# AugmentedStethoscope_v1.net
KiCad netlist of a schematic drawn in EAGLE
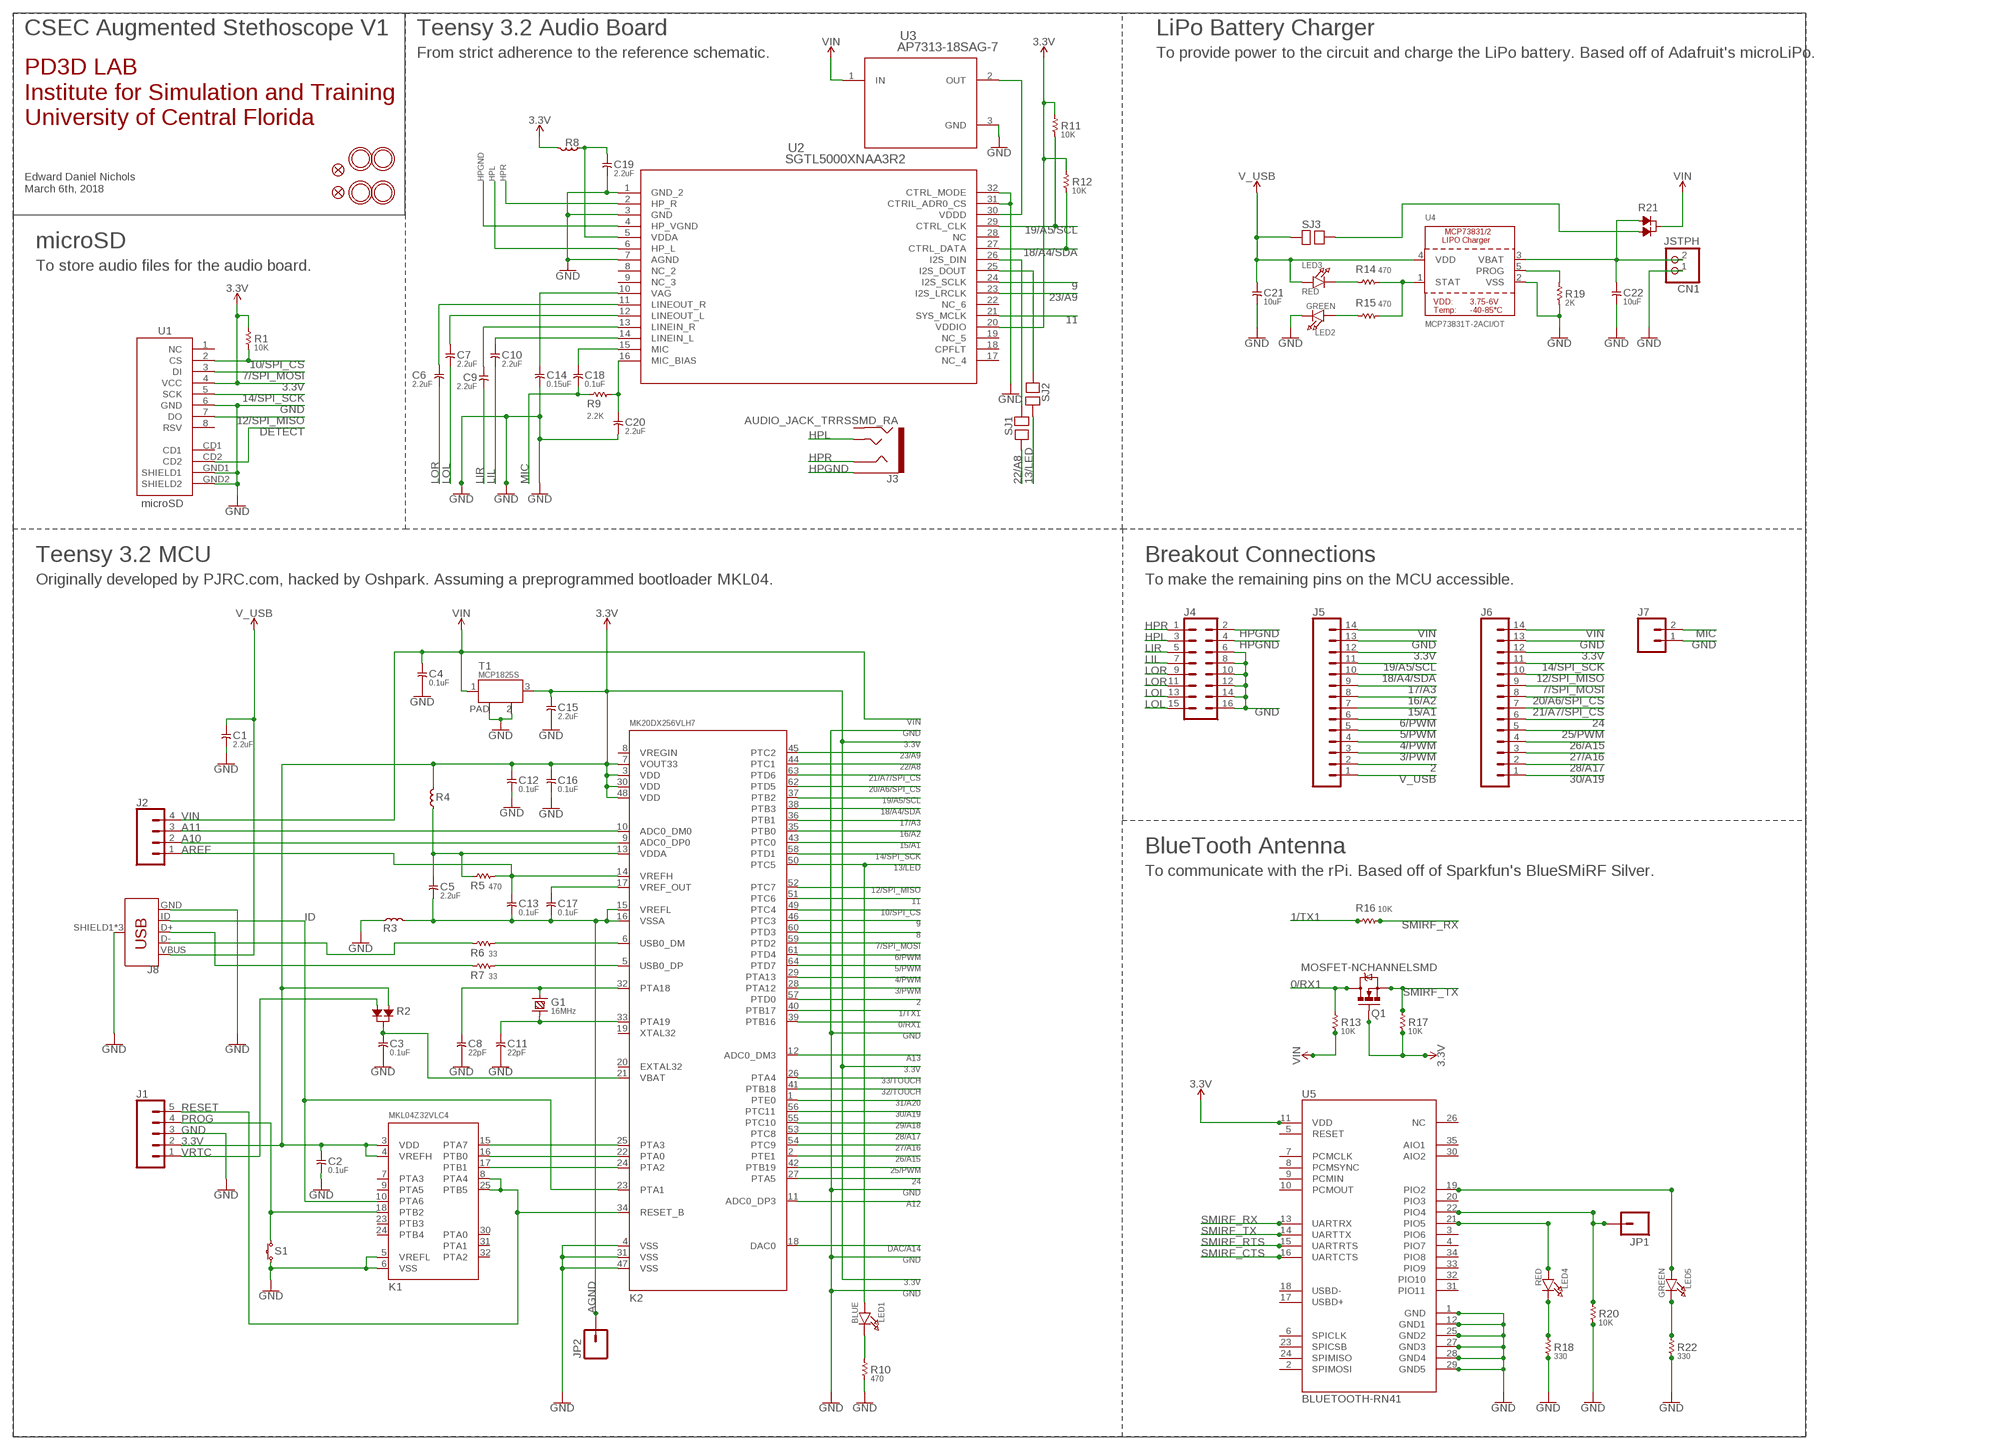
[diagram p0: schematic, sheet 1]

(export (version "E")
  (design (tool "Eeschema 10.0.6"))
  (components
    (comp (ref "C1")
      (value "2.2uF")
      (footprint "eagle-import:C0805")
      (fields (field (name "MF") "Taiyo Yuden") (field (name "MPN") "TMK212B7225KG-TR"))
      (libsource (lib "eagle-import") (part "CAPACITOR-2.2UF"))
    )
    (comp (ref "C2")
      (value "0.1uF")
      (footprint "eagle-import:C0603")
      (fields (field (name "MF") "Murata Electronics") (field (name "MPN") "GRM188R71C104KA01D"))
      (libsource (lib "eagle-import") (part "CAPACITOR-0.1UF"))
    )
    (comp (ref "C3")
      (value "0.1uF")
      (footprint "eagle-import:C0603")
      (fields (field (name "MF") "Murata Electronics") (field (name "MPN") "GRM188R71C104KA01D"))
      (libsource (lib "eagle-import") (part "CAPACITOR-0.1UF"))
    )
    (comp (ref "C4")
      (value "0.1uF")
      (footprint "eagle-import:C0603")
      (fields (field (name "MF") "Murata Electronics") (field (name "MPN") "GRM188R71C104KA01D"))
      (libsource (lib "eagle-import") (part "CAPACITOR-0.1UF"))
    )
    (comp (ref "C5")
      (value "2.2uF")
      (footprint "eagle-import:C0805")
      (fields (field (name "MF") "Taiyo Yuden") (field (name "MPN") "TMK212B7225KG-TR"))
      (libsource (lib "eagle-import") (part "CAPACITOR-2.2UF"))
    )
    (comp (ref "C6")
      (value "2.2uF")
      (footprint "eagle-import:C0805")
      (fields (field (name "MF") "Taiyo Yuden") (field (name "MPN") "TMK212B7225KG-TR"))
      (libsource (lib "eagle-import") (part "CAPACITOR-2.2UF"))
    )
    (comp (ref "C7")
      (value "2.2uF")
      (footprint "eagle-import:C0805")
      (fields (field (name "MF") "Taiyo Yuden") (field (name "MPN") "TMK212B7225KG-TR"))
      (libsource (lib "eagle-import") (part "CAPACITOR-2.2UF"))
    )
    (comp (ref "C8")
      (value "22pF")
      (footprint "eagle-import:C0603")
      (fields (field (name "MF") "Vishay / Vitramon") (field (name "MPN") "VJ0603A220JXACW1BC"))
      (libsource (lib "eagle-import") (part "CAPACITOR-22PF"))
    )
    (comp (ref "C9")
      (value "2.2uF")
      (footprint "eagle-import:C0805")
      (fields (field (name "MF") "Taiyo Yuden") (field (name "MPN") "TMK212B7225KG-TR"))
      (libsource (lib "eagle-import") (part "CAPACITOR-2.2UF"))
    )
    (comp (ref "C10")
      (value "2.2uF")
      (footprint "eagle-import:C0805")
      (fields (field (name "MF") "Taiyo Yuden") (field (name "MPN") "TMK212B7225KG-TR"))
      (libsource (lib "eagle-import") (part "CAPACITOR-2.2UF"))
    )
    (comp (ref "C11")
      (value "22pF")
      (footprint "eagle-import:C0603")
      (fields (field (name "MF") "Vishay / Vitramon") (field (name "MPN") "VJ0603A220JXACW1BC"))
      (libsource (lib "eagle-import") (part "CAPACITOR-22PF"))
    )
    (comp (ref "C12")
      (value "0.1uF")
      (footprint "eagle-import:C0603")
      (fields (field (name "MF") "Murata Electronics") (field (name "MPN") "GRM188R71C104KA01D"))
      (libsource (lib "eagle-import") (part "CAPACITOR-0.1UF"))
    )
    (comp (ref "C13")
      (value "0.1uF")
      (footprint "eagle-import:C0603")
      (fields (field (name "MF") "Murata Electronics") (field (name "MPN") "GRM188R71C104KA01D"))
      (libsource (lib "eagle-import") (part "CAPACITOR-0.1UF"))
    )
    (comp (ref "C14")
      (value "0.15uF")
      (footprint "eagle-import:C0805")
      (fields (field (name "MF") "Taiyo Yuden") (field (name "MPN") "TMK212B7225KG-TR"))
      (libsource (lib "eagle-import") (part "CAPACITOR-2.2UF"))
    )
    (comp (ref "C15")
      (value "2.2uF")
      (footprint "eagle-import:C0805")
      (fields (field (name "MF") "Taiyo Yuden") (field (name "MPN") "TMK212B7225KG-TR"))
      (libsource (lib "eagle-import") (part "CAPACITOR-2.2UF"))
    )
    (comp (ref "C16")
      (value "0.1uF")
      (footprint "eagle-import:C0603")
      (fields (field (name "MF") "Murata Electronics") (field (name "MPN") "GRM188R71C104KA01D"))
      (libsource (lib "eagle-import") (part "CAPACITOR-0.1UF"))
    )
    (comp (ref "C17")
      (value "0.1uF")
      (footprint "eagle-import:C0603")
      (fields (field (name "MF") "Murata Electronics") (field (name "MPN") "GRM188R71C104KA01D"))
      (libsource (lib "eagle-import") (part "CAPACITOR-0.1UF"))
    )
    (comp (ref "C18")
      (value "0.1uF")
      (footprint "eagle-import:C0805")
      (fields (field (name "MF") "Taiyo Yuden") (field (name "MPN") "TMK212B7225KG-TR"))
      (libsource (lib "eagle-import") (part "CAPACITOR-2.2UF"))
    )
    (comp (ref "C19")
      (value "2.2uF")
      (footprint "eagle-import:C0805")
      (fields (field (name "MF") "Taiyo Yuden") (field (name "MPN") "TMK212B7225KG-TR"))
      (libsource (lib "eagle-import") (part "CAPACITOR-2.2UF"))
    )
    (comp (ref "C20")
      (value "2.2uF")
      (footprint "eagle-import:C0805")
      (fields (field (name "MF") "Taiyo Yuden") (field (name "MPN") "TMK212B7225KG-TR"))
      (libsource (lib "eagle-import") (part "CAPACITOR-2.2UF"))
    )
    (comp (ref "C21")
      (value "10uF")
      (footprint "eagle-import:C0603")
      (fields (field (name "MF") "Murata Electronics") (field (name "MPN") "GRM188R71C104KA01D"))
      (libsource (lib "eagle-import") (part "CAPACITOR-0.1UF"))
    )
    (comp (ref "C22")
      (value "10uF")
      (footprint "eagle-import:C0603")
      (fields (field (name "MF") "Murata Electronics") (field (name "MPN") "GRM188R71C104KA01D"))
      (libsource (lib "eagle-import") (part "CAPACITOR-0.1UF"))
    )
    (comp (ref "CN1")
      (value "JSTPH")
      (footprint "eagle-import:JSTPH2")
      (libsource (lib "eagle-import") (part "JST_2PIN"))
    )
    (comp (ref "FID2")
      (value "FIDUCIAL\"\"")
      (footprint "eagle-import:FIDUCIAL_1MM")
      (libsource (lib "eagle-import") (part "FIDUCIAL{dblquote}{dblquote}"))
    )
    (comp (ref "FID3")
      (value "FIDUCIAL\"\"")
      (footprint "eagle-import:FIDUCIAL_1MM")
      (fields (field (name "BOM") "EXCLUDE"))
      (libsource (lib "eagle-import") (part "FIDUCIAL{dblquote}{dblquote}"))
    )
    (comp (ref "G1")
      (value "16MHz")
      (footprint "eagle-import:HC49US")
      (fields (field (name "MF") "ABRACON") (field (name "MPN") "ABL-16.000MHz-B1U"))
      (libsource (lib "eagle-import") (part "CRYSTAL-HC49US"))
    )
    (comp (ref "J1")
      (value "CONN_05")
      (footprint "eagle-import:1X05")
      (libsource (lib "eagle-import") (part "CONN_05"))
    )
    (comp (ref "J2")
      (value "CONN_04")
      (footprint "eagle-import:1X04")
      (libsource (lib "eagle-import") (part "CONN_04"))
    )
    (comp (ref "J3")
      (value "AUDIO_JACK_TRRSSMD_RA")
      (footprint "eagle-import:AUDIO_JACK_3.5MM_TRRS_SMD_RA")
      (libsource (lib "eagle-import") (part "AUDIO_JACK_TRRSSMD_RA"))
    )
    (comp (ref "J4")
      (value "CONN_08X2")
      (footprint "eagle-import:2X8")
      (libsource (lib "eagle-import") (part "CONN_08X2"))
    )
    (comp (ref "J5")
      (value "CONN_14")
      (footprint "eagle-import:1X14")
      (libsource (lib "eagle-import") (part "CONN_14"))
    )
    (comp (ref "J6")
      (value "CONN_14")
      (footprint "eagle-import:1X14")
      (libsource (lib "eagle-import") (part "CONN_14"))
    )
    (comp (ref "J7")
      (value "CONN_02")
      (footprint "eagle-import:1X02")
      (libsource (lib "eagle-import") (part "CONN_02"))
    )
    (comp (ref "J8")
      (value "USB_MICRO-B_FEMALE-SMT")
      (footprint "eagle-import:USB-B-MICRO-SMD")
      (libsource (lib "eagle-import") (part "USB_MICRO-B_FEMALE-SMT"))
    )
    (comp (ref "JP1")
      (value "M01SMDNS")
      (footprint "eagle-import:1X01NS")
      (libsource (lib "eagle-import") (part "M01SMDNS"))
    )
    (comp (ref "JP2")
      (value "M01SMDNS")
      (footprint "eagle-import:1X01NS")
      (libsource (lib "eagle-import") (part "M01SMDNS"))
    )
    (comp (ref "K1")
      (value "MKL04Z32VLC4")
      (footprint "eagle-import:LQFP32-08")
      (fields (field (name "MF") "PJRC") (field (name "MPN") "IC_MKL04Z32_TQFP32"))
      (libsource (lib "eagle-import") (part "MKL04Z32VLC4"))
    )
    (comp (ref "K2")
      (value "MK20DX256VLH7")
      (footprint "eagle-import:LQFP64-05")
      (fields (field (name "MF") "NXP"))
      (libsource (lib "eagle-import") (part "MK20DX256VLH7"))
    )
    (comp (ref "LED1")
      (value "BLUE")
      (footprint "eagle-import:CHIPLED_0805")
      (libsource (lib "eagle-import") (part "LED0805"))
    )
    (comp (ref "LED2")
      (value "GREEN")
      (footprint "eagle-import:CHIPLED_0805")
      (libsource (lib "eagle-import") (part "LED0805"))
    )
    (comp (ref "LED3")
      (value "RED")
      (footprint "eagle-import:CHIPLED_0805")
      (libsource (lib "eagle-import") (part "LED0805"))
    )
    (comp (ref "LED4")
      (value "RED")
      (footprint "eagle-import:CHIPLED_0805")
      (libsource (lib "eagle-import") (part "LED0805"))
    )
    (comp (ref "LED5")
      (value "GREEN")
      (footprint "eagle-import:CHIPLED_0805")
      (libsource (lib "eagle-import") (part "LED0805"))
    )
    (comp (ref "Q1")
      (value "MOSFET-NCHANNELSMD")
      (footprint "eagle-import:SOT23-3")
      (libsource (lib "eagle-import") (part "MOSFET-NCHANNELSMD"))
    )
    (comp (ref "R1")
      (value "10K")
      (footprint "eagle-import:R0603")
      (fields (field (name "MF") "Vishay") (field (name "MPN") "CRCW0603470RFKEA"))
      (libsource (lib "eagle-import") (part "RESISTOR-470R"))
    )
    (comp (ref "R2")
      (value "DIODE_DUAL")
      (footprint "eagle-import:SOT-23")
      (fields (field (name "MF") "NXP Semiconductors") (field (name "MPN") "BAT54C,215"))
      (libsource (lib "eagle-import") (part "DIODE_DUAL"))
    )
    (comp (ref "R3")
      (value "FERRITE")
      (footprint "eagle-import:L0603")
      (fields (field (name "MF") "Murata Electronics") (field (name "MPN") " BLM18AG601SN1D"))
      (libsource (lib "eagle-import") (part "FERRITE"))
    )
    (comp (ref "R4")
      (value "FERRITE")
      (footprint "eagle-import:L0603")
      (fields (field (name "MF") "Murata Electronics") (field (name "MPN") " BLM18AG601SN1D"))
      (libsource (lib "eagle-import") (part "FERRITE"))
    )
    (comp (ref "R5")
      (value "470")
      (footprint "eagle-import:R0603")
      (fields (field (name "MF") "Vishay") (field (name "MPN") "CRCW0603470RFKEA"))
      (libsource (lib "eagle-import") (part "RESISTOR-470R"))
    )
    (comp (ref "R6")
      (value "33")
      (footprint "eagle-import:R0603")
      (fields (field (name "MF") "Panasonic") (field (name "MPN") "ERJ-PA3F33R0V"))
      (libsource (lib "eagle-import") (part "RESISTOR-33R"))
    )
    (comp (ref "R7")
      (value "33")
      (footprint "eagle-import:R0603")
      (fields (field (name "MF") "Panasonic") (field (name "MPN") "ERJ-PA3F33R0V"))
      (libsource (lib "eagle-import") (part "RESISTOR-33R"))
    )
    (comp (ref "R8")
      (value "FERRITE")
      (footprint "eagle-import:L0603")
      (fields (field (name "MF") "Murata Electronics") (field (name "MPN") " BLM18AG601SN1D"))
      (libsource (lib "eagle-import") (part "FERRITE"))
    )
    (comp (ref "R9")
      (value "2.2K")
      (footprint "eagle-import:R0603")
      (fields (field (name "MF") "Vishay") (field (name "MPN") "CRCW0603470RFKEA"))
      (libsource (lib "eagle-import") (part "RESISTOR-470R"))
    )
    (comp (ref "R10")
      (value "470")
      (footprint "eagle-import:R0603")
      (fields (field (name "MF") "Vishay") (field (name "MPN") "CRCW0603470RFKEA"))
      (libsource (lib "eagle-import") (part "RESISTOR-470R"))
    )
    (comp (ref "R11")
      (value "10K")
      (footprint "eagle-import:R0603")
      (fields (field (name "MF") "Vishay") (field (name "MPN") "CRCW0603470RFKEA"))
      (libsource (lib "eagle-import") (part "RESISTOR-470R"))
    )
    (comp (ref "R12")
      (value "10K")
      (footprint "eagle-import:R0603")
      (fields (field (name "MF") "Vishay") (field (name "MPN") "CRCW0603470RFKEA"))
      (libsource (lib "eagle-import") (part "RESISTOR-470R"))
    )
    (comp (ref "R13")
      (value "10K")
      (footprint "eagle-import:R0603")
      (fields (field (name "MF") "Vishay") (field (name "MPN") "CRCW0603470RFKEA"))
      (libsource (lib "eagle-import") (part "RESISTOR-470R"))
    )
    (comp (ref "R14")
      (value "470")
      (footprint "eagle-import:R0603")
      (fields (field (name "MF") "Panasonic") (field (name "MPN") "ERJ-PA3F33R0V"))
      (libsource (lib "eagle-import") (part "RESISTOR-33R"))
    )
    (comp (ref "R15")
      (value "470")
      (footprint "eagle-import:R0603")
      (fields (field (name "MF") "Panasonic") (field (name "MPN") "ERJ-PA3F33R0V"))
      (libsource (lib "eagle-import") (part "RESISTOR-33R"))
    )
    (comp (ref "R16")
      (value "10K")
      (footprint "eagle-import:R0603")
      (fields (field (name "MF") "Panasonic") (field (name "MPN") "ERJ-PA3F33R0V"))
      (libsource (lib "eagle-import") (part "RESISTOR-33R"))
    )
    (comp (ref "R17")
      (value "10K")
      (footprint "eagle-import:R0603")
      (fields (field (name "MF") "Vishay") (field (name "MPN") "CRCW0603470RFKEA"))
      (libsource (lib "eagle-import") (part "RESISTOR-470R"))
    )
    (comp (ref "R18")
      (value "330")
      (footprint "eagle-import:R0603")
      (fields (field (name "MF") "Vishay") (field (name "MPN") "CRCW0603470RFKEA"))
      (libsource (lib "eagle-import") (part "RESISTOR-470R"))
    )
    (comp (ref "R19")
      (value "2K")
      (footprint "eagle-import:R0603")
      (fields (field (name "MF") "Vishay") (field (name "MPN") "CRCW0603470RFKEA"))
      (libsource (lib "eagle-import") (part "RESISTOR-470R"))
    )
    (comp (ref "R20")
      (value "10K")
      (footprint "eagle-import:R0603")
      (fields (field (name "MF") "Vishay") (field (name "MPN") "CRCW0603470RFKEA"))
      (libsource (lib "eagle-import") (part "RESISTOR-470R"))
    )
    (comp (ref "R21")
      (value "DIODE_DUAL")
      (footprint "eagle-import:SOT-23")
      (fields (field (name "MF") "NXP Semiconductors") (field (name "MPN") "BAT54C,215"))
      (libsource (lib "eagle-import") (part "DIODE_DUAL"))
    )
    (comp (ref "R22")
      (value "330")
      (footprint "eagle-import:R0603")
      (fields (field (name "MF") "Vishay") (field (name "MPN") "CRCW0603470RFKEA"))
      (libsource (lib "eagle-import") (part "RESISTOR-470R"))
    )
    (comp (ref "S1")
      (value "TACT_SWITCH")
      (footprint "eagle-import:ALPS_SKHH")
      (fields (field (name "MF") "ALPS") (field (name "MPN") "SKHHPKA010"))
      (libsource (lib "eagle-import") (part "TACT_SWITCH"))
    )
    (comp (ref "SJ1")
      (value "SOLDERJUMPER")
      (footprint "eagle-import:SOLDERJUMPER")
      (libsource (lib "eagle-import") (part "SOLDERJUMPER"))
    )
    (comp (ref "SJ2")
      (value "SOLDERJUMPER")
      (footprint "eagle-import:SOLDERJUMPER")
      (libsource (lib "eagle-import") (part "SOLDERJUMPER"))
    )
    (comp (ref "SJ3")
      (value "SOLDERJUMPER")
      (footprint "eagle-import:SOLDERJUMPER")
      (libsource (lib "eagle-import") (part "SOLDERJUMPER"))
    )
    (comp (ref "T1")
      (value "MCP1825S")
      (footprint "eagle-import:SOT-223")
      (fields (field (name "MF") "Microchip Technology") (field (name "MPN") "MCP1825S-3302E/DB"))
      (libsource (lib "eagle-import") (part "LDO"))
    )
    (comp (ref "U$1")
      (value "MOUNTINGHOLE2.5")
      (footprint "eagle-import:MOUNTINGHOLE_2.5_PLATED")
      (libsource (lib "eagle-import") (part "MOUNTINGHOLE2.5"))
    )
    (comp (ref "U$15")
      (value "MOUNTINGHOLE2.5")
      (footprint "eagle-import:MOUNTINGHOLE_2.5_PLATED")
      (libsource (lib "eagle-import") (part "MOUNTINGHOLE2.5"))
    )
    (comp (ref "U$17")
      (value "MOUNTINGHOLE2.5")
      (footprint "eagle-import:MOUNTINGHOLE_2.5_PLATED")
      (libsource (lib "eagle-import") (part "MOUNTINGHOLE2.5"))
    )
    (comp (ref "U$18")
      (value "MOUNTINGHOLE2.5")
      (footprint "eagle-import:MOUNTINGHOLE_2.5_PLATED")
      (libsource (lib "eagle-import") (part "MOUNTINGHOLE2.5"))
    )
    (comp (ref "U1")
      (value "microSD")
      (footprint "eagle-import:MICRO-SD-SOCKET-PP")
      (libsource (lib "eagle-import") (part "USD-SOCKETSMD"))
    )
    (comp (ref "U2")
      (value "SGTL5000XNAA3R2")
      (footprint "eagle-import:QFN32")
      (libsource (lib "eagle-import") (part "SGTL5000XNAA3R2"))
    )
    (comp (ref "U3")
      (value "AP7313-18SAG-7")
      (footprint "eagle-import:SOT-23")
      (fields (field (name "MANUFACTURER_PART_NUMBER") "AP731318SAG7"))
      (libsource (lib "eagle-import") (part "AP7313-18SAG-7"))
    )
    (comp (ref "U4")
      (value "MCP73831T-2ACI/OT")
      (footprint "eagle-import:SOT23-5")
      (libsource (lib "eagle-import") (part "MCP73831/2"))
    )
    (comp (ref "U5")
      (value "BLUETOOTH-RN41")
      (footprint "eagle-import:RN41")
      (libsource (lib "eagle-import") (part "BLUETOOTH-RN41{dblquote}"))
    )
  )
  (nets
    (net (code "1") (name "/0{slash}RX1") (class "Default")
      (node (ref "K2") (pin "39") (pinfunction "PTB16_39") (pintype "bidirectional"))
      (node (ref "Q1") (pin "3") (pinfunction "D_3") (pintype "passive"))
      (node (ref "R13") (pin "2") (pinfunction "2_2") (pintype "passive"))
    )
    (net (code "2") (name "/1{slash}TX1") (class "Default")
      (node (ref "K2") (pin "40") (pinfunction "PTB17_40") (pintype "bidirectional"))
      (node (ref "R16") (pin "1") (pinfunction "1_1") (pintype "passive"))
    )
    (net (code "3") (name "/2") (class "Default")
      (node (ref "J5") (pin "2") (pinfunction "2_2") (pintype "passive"))
      (node (ref "K2") (pin "57") (pinfunction "PTD0_57") (pintype "bidirectional"))
    )
    (net (code "4") (name "/3{slash}PWM") (class "Default")
      (node (ref "J5") (pin "3") (pinfunction "3_3") (pintype "passive"))
      (node (ref "K2") (pin "28") (pinfunction "PTA12_28") (pintype "bidirectional"))
    )
    (net (code "5") (name "/4{slash}PWM") (class "Default")
      (node (ref "J5") (pin "4") (pinfunction "4_4") (pintype "passive"))
      (node (ref "K2") (pin "29") (pinfunction "PTA13_29") (pintype "bidirectional"))
    )
    (net (code "6") (name "/5{slash}PWM") (class "Default")
      (node (ref "J5") (pin "5") (pinfunction "5_5") (pintype "passive"))
      (node (ref "K2") (pin "64") (pinfunction "PTD7_64") (pintype "bidirectional"))
    )
    (net (code "7") (name "/6{slash}PWM") (class "Default")
      (node (ref "J5") (pin "6") (pinfunction "6_6") (pintype "passive"))
      (node (ref "K2") (pin "61") (pinfunction "PTD4_61") (pintype "bidirectional"))
    )
    (net (code "8") (name "/7{slash}SPI_MOSI") (class "Default")
      (node (ref "J6") (pin "9") (pinfunction "9_9") (pintype "passive"))
      (node (ref "K2") (pin "59") (pinfunction "PTD2_59") (pintype "bidirectional"))
      (node (ref "U1") (pin "3") (pinfunction "DI_3") (pintype "bidirectional"))
    )
    (net (code "9") (name "/8") (class "Default")
      (node (ref "K2") (pin "60") (pinfunction "PTD3_60") (pintype "bidirectional"))
    )
    (net (code "10") (name "/9") (class "Default")
      (node (ref "K2") (pin "46") (pinfunction "PTC3_46") (pintype "bidirectional"))
      (node (ref "U2") (pin "24") (pinfunction "I2S_SCLK_24") (pintype "passive"))
    )
    (net (code "11") (name "/10{slash}SPI_CS") (class "Default")
      (node (ref "K2") (pin "49") (pinfunction "PTC4_49") (pintype "bidirectional"))
      (node (ref "R1") (pin "1") (pinfunction "1_1") (pintype "passive"))
      (node (ref "U1") (pin "2") (pinfunction "CS_2") (pintype "bidirectional"))
    )
    (net (code "12") (name "/11") (class "Default")
      (node (ref "K2") (pin "51") (pinfunction "PTC6_51") (pintype "bidirectional"))
      (node (ref "U2") (pin "21") (pinfunction "SYS_MCLK_21") (pintype "passive"))
    )
    (net (code "13") (name "/12{slash}SPI_MISO") (class "Default")
      (node (ref "J6") (pin "10") (pinfunction "10_10") (pintype "passive"))
      (node (ref "K2") (pin "52") (pinfunction "PTC7_52") (pintype "bidirectional"))
      (node (ref "U1") (pin "7") (pinfunction "DO_7") (pintype "bidirectional"))
    )
    (net (code "14") (name "/13{slash}LED") (class "Default")
      (node (ref "K2") (pin "50") (pinfunction "PTC5_50") (pintype "bidirectional"))
      (node (ref "LED1") (pin "A") (pinfunction "A_A") (pintype "passive"))
      (node (ref "SJ2") (pin "2") (pinfunction "2_2") (pintype "passive"))
    )
    (net (code "15") (name "/14{slash}SPI_SCK") (class "Default")
      (node (ref "J6") (pin "11") (pinfunction "11_11") (pintype "passive"))
      (node (ref "K2") (pin "58") (pinfunction "PTD1_58") (pintype "bidirectional"))
      (node (ref "U1") (pin "5") (pinfunction "SCK_5") (pintype "bidirectional"))
    )
    (net (code "16") (name "/15{slash}A1") (class "Default")
      (node (ref "J5") (pin "7") (pinfunction "7_7") (pintype "passive"))
      (node (ref "K2") (pin "43") (pinfunction "PTC0_43") (pintype "bidirectional"))
    )
    (net (code "17") (name "/16{slash}A2") (class "Default")
      (node (ref "J5") (pin "8") (pinfunction "8_8") (pintype "passive"))
      (node (ref "K2") (pin "35") (pinfunction "PTB0_35") (pintype "bidirectional"))
    )
    (net (code "18") (name "/17{slash}A3") (class "Default")
      (node (ref "J5") (pin "9") (pinfunction "9_9") (pintype "passive"))
      (node (ref "K2") (pin "36") (pinfunction "PTB1_36") (pintype "bidirectional"))
    )
    (net (code "19") (name "/18{slash}A4{slash}SDA") (class "Default")
      (node (ref "J5") (pin "10") (pinfunction "10_10") (pintype "passive"))
      (node (ref "K2") (pin "38") (pinfunction "PTB3_38") (pintype "bidirectional"))
      (node (ref "R12") (pin "1") (pinfunction "1_1") (pintype "passive"))
      (node (ref "U2") (pin "27") (pinfunction "CTRL_DATA_27") (pintype "passive"))
    )
    (net (code "20") (name "/19{slash}A5{slash}SCL") (class "Default")
      (node (ref "J5") (pin "11") (pinfunction "11_11") (pintype "passive"))
      (node (ref "K2") (pin "37") (pinfunction "PTB2_37") (pintype "bidirectional"))
      (node (ref "R11") (pin "1") (pinfunction "1_1") (pintype "passive"))
      (node (ref "U2") (pin "29") (pinfunction "CTRL_CLK_29") (pintype "passive"))
    )
    (net (code "21") (name "/20{slash}A6{slash}SPI_CS") (class "Default")
      (node (ref "J6") (pin "8") (pinfunction "8_8") (pintype "passive"))
      (node (ref "K2") (pin "62") (pinfunction "PTD5_62") (pintype "bidirectional"))
    )
    (net (code "22") (name "/21{slash}A7{slash}SPI_CS") (class "Default")
      (node (ref "J6") (pin "7") (pinfunction "7_7") (pintype "passive"))
      (node (ref "K2") (pin "63") (pinfunction "PTD6_63") (pintype "bidirectional"))
    )
    (net (code "23") (name "/22{slash}A8") (class "Default")
      (node (ref "K2") (pin "44") (pinfunction "PTC1_44") (pintype "bidirectional"))
      (node (ref "SJ1") (pin "2") (pinfunction "2_2") (pintype "passive"))
    )
    (net (code "24") (name "/23{slash}A9") (class "Default")
      (node (ref "K2") (pin "45") (pinfunction "PTC2_45") (pintype "bidirectional"))
      (node (ref "U2") (pin "23") (pinfunction "I2S_LRCLK_23") (pintype "passive"))
    )
    (net (code "25") (name "/24") (class "Default")
      (node (ref "J6") (pin "6") (pinfunction "6_6") (pintype "passive"))
      (node (ref "K2") (pin "27") (pinfunction "PTA5_27") (pintype "bidirectional"))
    )
    (net (code "26") (name "/25{slash}PWM") (class "Default")
      (node (ref "J6") (pin "5") (pinfunction "5_5") (pintype "passive"))
      (node (ref "K2") (pin "42") (pinfunction "PTB19_42") (pintype "bidirectional"))
    )
    (net (code "27") (name "/26{slash}A15") (class "Default")
      (node (ref "J6") (pin "4") (pinfunction "4_4") (pintype "passive"))
      (node (ref "K2") (pin "2") (pinfunction "PTE1_2") (pintype "bidirectional"))
    )
    (net (code "28") (name "/27{slash}A16") (class "Default")
      (node (ref "J6") (pin "3") (pinfunction "3_3") (pintype "passive"))
      (node (ref "K2") (pin "54") (pinfunction "PTC9_54") (pintype "bidirectional"))
    )
    (net (code "29") (name "/28{slash}A17") (class "Default")
      (node (ref "J6") (pin "2") (pinfunction "2_2") (pintype "passive"))
      (node (ref "K2") (pin "53") (pinfunction "PTC8_53") (pintype "bidirectional"))
    )
    (net (code "30") (name "/29{slash}A18") (class "Default")
      (node (ref "K2") (pin "55") (pinfunction "PTC10_55") (pintype "bidirectional"))
    )
    (net (code "31") (name "/30{slash}A19") (class "Default")
      (node (ref "J6") (pin "1") (pinfunction "1_1") (pintype "passive"))
      (node (ref "K2") (pin "56") (pinfunction "PTC11_56") (pintype "bidirectional"))
    )
    (net (code "32") (name "/31{slash}A20") (class "Default")
      (node (ref "K2") (pin "1") (pinfunction "PTE0_1") (pintype "bidirectional"))
    )
    (net (code "33") (name "/32{slash}TOUCH") (class "Default")
      (node (ref "K2") (pin "41") (pinfunction "PTB18_41") (pintype "bidirectional"))
    )
    (net (code "34") (name "/33{slash}TOUCH") (class "Default")
      (node (ref "K2") (pin "26") (pinfunction "PTA4_26") (pintype "bidirectional"))
    )
    (net (code "35") (name "/A10") (class "Default")
      (node (ref "J2") (pin "2") (pinfunction "2_2") (pintype "passive"))
      (node (ref "K2") (pin "9") (pinfunction "ADC0_DP0_9") (pintype "bidirectional"))
    )
    (net (code "36") (name "/A11") (class "Default")
      (node (ref "J2") (pin "3") (pinfunction "3_3") (pintype "passive"))
      (node (ref "K2") (pin "10") (pinfunction "ADC0_DM0_10") (pintype "bidirectional"))
    )
    (net (code "37") (name "/A12") (class "Default")
      (node (ref "K2") (pin "11") (pinfunction "ADC0_DP3_11") (pintype "bidirectional"))
    )
    (net (code "38") (name "/A13") (class "Default")
      (node (ref "K2") (pin "12") (pinfunction "ADC0_DM3_12") (pintype "bidirectional"))
    )
    (net (code "39") (name "/AGND") (class "Default")
      (node (ref "C13") (pin "2") (pinfunction "2_2") (pintype "passive"))
      (node (ref "C17") (pin "2") (pinfunction "2_2") (pintype "passive"))
      (node (ref "C5") (pin "2") (pinfunction "2_2") (pintype "passive"))
      (node (ref "JP2") (pin "1") (pinfunction "1_1") (pintype "passive"))
      (node (ref "K2") (pin "15") (pinfunction "VREFL_15") (pintype "bidirectional"))
      (node (ref "K2") (pin "16") (pinfunction "VSSA_16") (pintype "bidirectional"))
      (node (ref "R3") (pin "2") (pinfunction "2_2") (pintype "passive"))
    )
    (net (code "40") (name "/AREF") (class "Default")
      (node (ref "C13") (pin "1") (pinfunction "1_1") (pintype "passive"))
      (node (ref "J2") (pin "1") (pinfunction "1_1") (pintype "passive"))
      (node (ref "K2") (pin "14") (pinfunction "VREFH_14") (pintype "bidirectional"))
      (node (ref "R5") (pin "2") (pinfunction "2_2") (pintype "passive"))
    )
    (net (code "41") (name "/DAC{slash}A14") (class "Default")
      (node (ref "K2") (pin "18") (pinfunction "DAC0_18") (pintype "bidirectional"))
    )
    (net (code "42") (name "/DETECT") (class "Default")
      (node (ref "U1") (pin "CD2") (pinfunction "CD2_CD2") (pintype "bidirectional"))
    )
    (net (code "43") (name "/HPGND") (class "Default")
      (node (ref "J3") (pin "EARTH") (pinfunction "EARTH_EARTH") (pintype "bidirectional"))
      (node (ref "J4") (pin "2") (pinfunction "2_2") (pintype "passive"))
      (node (ref "J4") (pin "4") (pinfunction "4_4") (pintype "passive"))
      (node (ref "U2") (pin "4") (pinfunction "HP_VGND_4") (pintype "power_in"))
    )
    (net (code "44") (name "/HPL") (class "Default")
      (node (ref "J3") (pin "TIP") (pinfunction "TIP_TIP") (pintype "bidirectional"))
      (node (ref "J4") (pin "3") (pinfunction "3_3") (pintype "passive"))
      (node (ref "U2") (pin "6") (pinfunction "HP_L_6") (pintype "output"))
    )
    (net (code "45") (name "/HPR") (class "Default")
      (node (ref "J3") (pin "RING1") (pinfunction "RING1_RING1") (pintype "bidirectional"))
      (node (ref "J4") (pin "1") (pinfunction "1_1") (pintype "passive"))
      (node (ref "U2") (pin "2") (pinfunction "HP_R_2") (pintype "output"))
    )
    (net (code "46") (name "/ID") (class "Default")
      (node (ref "J8") (pin "ID") (pinfunction "ID_ID") (pintype "bidirectional"))
      (node (ref "K1") (pin "10") (pinfunction "PTA6_10") (pintype "bidirectional"))
      (node (ref "K2") (pin "23") (pinfunction "PTA1_23") (pintype "bidirectional"))
    )
    (net (code "47") (name "/LIL") (class "Default")
      (node (ref "C10") (pin "2") (pinfunction "2_2") (pintype "passive"))
      (node (ref "J4") (pin "7") (pinfunction "7_7") (pintype "passive"))
    )
    (net (code "48") (name "/LIR") (class "Default")
      (node (ref "C9") (pin "2") (pinfunction "2_2") (pintype "passive"))
      (node (ref "J4") (pin "5") (pinfunction "5_5") (pintype "passive"))
    )
    (net (code "49") (name "/LOL") (class "Default")
      (node (ref "C7") (pin "2") (pinfunction "2_2") (pintype "passive"))
      (node (ref "J4") (pin "13") (pinfunction "13_13") (pintype "passive"))
      (node (ref "J4") (pin "15") (pinfunction "15_15") (pintype "passive"))
    )
    (net (code "50") (name "/LOR") (class "Default")
      (node (ref "C6") (pin "2") (pinfunction "2_2") (pintype "passive"))
      (node (ref "J4") (pin "11") (pinfunction "11_11") (pintype "passive"))
      (node (ref "J4") (pin "9") (pinfunction "9_9") (pintype "passive"))
    )
    (net (code "51") (name "/MIC") (class "Default")
      (node (ref "C18") (pin "2") (pinfunction "2_2") (pintype "passive"))
      (node (ref "J7") (pin "2") (pinfunction "2_2") (pintype "passive"))
      (node (ref "R9") (pin "1") (pinfunction "1_1") (pintype "passive"))
    )
    (net (code "52") (name "/PROG") (class "Default")
      (node (ref "J1") (pin "4") (pinfunction "4_4") (pintype "passive"))
      (node (ref "K1") (pin "18") (pinfunction "PTB2_18") (pintype "bidirectional"))
      (node (ref "S1") (pin "1") (pinfunction "1_1") (pintype "passive"))
      (node (ref "S1") (pin "2") (pinfunction "1_2") (pintype "passive"))
    )
    (net (code "53") (name "/RESET") (class "Default")
      (node (ref "J1") (pin "5") (pinfunction "5_5") (pintype "passive"))
      (node (ref "K1") (pin "25") (pinfunction "PTB5_25") (pintype "bidirectional"))
      (node (ref "K1") (pin "8") (pinfunction "PTA4_8") (pintype "bidirectional"))
      (node (ref "K2") (pin "34") (pinfunction "RESET_B_34") (pintype "bidirectional"))
    )
    (net (code "54") (name "/SMIRF_CTS") (class "Default")
      (node (ref "U5") (pin "16") (pinfunction "UARTCTS_16") (pintype "bidirectional"))
    )
    (net (code "55") (name "/SMIRF_RTS") (class "Default")
      (node (ref "U5") (pin "15") (pinfunction "UARTRTS_15") (pintype "bidirectional"))
    )
    (net (code "56") (name "/SMIRF_RX") (class "Default")
      (node (ref "R16") (pin "2") (pinfunction "2_2") (pintype "passive"))
      (node (ref "U5") (pin "13") (pinfunction "UARTRX_13") (pintype "bidirectional"))
    )
    (net (code "57") (name "/SMIRF_TX") (class "Default")
      (node (ref "Q1") (pin "2") (pinfunction "S_2") (pintype "passive"))
      (node (ref "R17") (pin "2") (pinfunction "2_2") (pintype "passive"))
      (node (ref "U5") (pin "14") (pinfunction "UARTTX_14") (pintype "bidirectional"))
    )
    (net (code "58") (name "/VRTC") (class "Default")
      (node (ref "J1") (pin "1") (pinfunction "1_1") (pintype "passive"))
      (node (ref "R2") (pin "2") (pinfunction "2_2") (pintype "bidirectional"))
    )
    (net (code "59") (name "3.3V") (class "Default")
      (node (ref "C12") (pin "1") (pinfunction "1_1") (pintype "passive"))
      (node (ref "C15") (pin "1") (pinfunction "1_1") (pintype "passive"))
      (node (ref "C16") (pin "1") (pinfunction "1_1") (pintype "passive"))
      (node (ref "C2") (pin "1") (pinfunction "1_1") (pintype "passive"))
      (node (ref "J1") (pin "2") (pinfunction "2_2") (pintype "passive"))
      (node (ref "J5") (pin "12") (pinfunction "12_12") (pintype "passive"))
      (node (ref "J6") (pin "12") (pinfunction "12_12") (pintype "passive"))
      (node (ref "K1") (pin "3") (pinfunction "VDD_3") (pintype "bidirectional"))
      (node (ref "K1") (pin "4") (pinfunction "VREFH_4") (pintype "bidirectional"))
      (node (ref "K2") (pin "3") (pinfunction "VDD_3") (pintype "bidirectional"))
      (node (ref "K2") (pin "30") (pinfunction "VDD_30") (pintype "bidirectional"))
      (node (ref "K2") (pin "48") (pinfunction "VDD_48") (pintype "bidirectional"))
      (node (ref "K2") (pin "7") (pinfunction "VOUT33_7") (pintype "bidirectional"))
      (node (ref "Q1") (pin "1") (pinfunction "G_1") (pintype "passive"))
      (node (ref "R1") (pin "2") (pinfunction "2_2") (pintype "passive"))
      (node (ref "R11") (pin "2") (pinfunction "2_2") (pintype "passive"))
      (node (ref "R12") (pin "2") (pinfunction "2_2") (pintype "passive"))
      (node (ref "R17") (pin "1") (pinfunction "1_1") (pintype "passive"))
      (node (ref "R2") (pin "1") (pinfunction "1_1") (pintype "bidirectional"))
      (node (ref "R4") (pin "2") (pinfunction "2_2") (pintype "passive"))
      (node (ref "R8") (pin "2") (pinfunction "2_2") (pintype "passive"))
      (node (ref "T1") (pin "3") (pinfunction "OUT_3") (pintype "bidirectional"))
      (node (ref "U1") (pin "4") (pinfunction "VCC_4") (pintype "bidirectional"))
      (node (ref "U2") (pin "20") (pinfunction "VDDIO_20") (pintype "power_in"))
      (node (ref "U5") (pin "11") (pinfunction "VDD_11") (pintype "bidirectional"))
    )
    (net (code "60") (name "GND") (class "Default")
      (node (ref "C1") (pin "2") (pinfunction "2_2") (pintype "passive"))
      (node (ref "C11") (pin "2") (pinfunction "2_2") (pintype "passive"))
      (node (ref "C12") (pin "2") (pinfunction "2_2") (pintype "passive"))
      (node (ref "C14") (pin "2") (pinfunction "2_2") (pintype "passive"))
      (node (ref "C15") (pin "2") (pinfunction "2_2") (pintype "passive"))
      (node (ref "C16") (pin "2") (pinfunction "2_2") (pintype "passive"))
      (node (ref "C19") (pin "2") (pinfunction "2_2") (pintype "passive"))
      (node (ref "C2") (pin "2") (pinfunction "2_2") (pintype "passive"))
      (node (ref "C20") (pin "2") (pinfunction "2_2") (pintype "passive"))
      (node (ref "C21") (pin "2") (pinfunction "2_2") (pintype "passive"))
      (node (ref "C22") (pin "2") (pinfunction "2_2") (pintype "passive"))
      (node (ref "C3") (pin "2") (pinfunction "2_2") (pintype "passive"))
      (node (ref "C4") (pin "2") (pinfunction "2_2") (pintype "passive"))
      (node (ref "C8") (pin "2") (pinfunction "2_2") (pintype "passive"))
      (node (ref "CN1") (pin "1") (pinfunction "1_1") (pintype "passive"))
      (node (ref "J1") (pin "3") (pinfunction "3_3") (pintype "passive"))
      (node (ref "J4") (pin "10") (pinfunction "10_10") (pintype "passive"))
      (node (ref "J4") (pin "12") (pinfunction "12_12") (pintype "passive"))
      (node (ref "J4") (pin "14") (pinfunction "14_14") (pintype "passive"))
      (node (ref "J4") (pin "16") (pinfunction "16_16") (pintype "passive"))
      (node (ref "J4") (pin "6") (pinfunction "6_6") (pintype "passive"))
      (node (ref "J4") (pin "8") (pinfunction "8_8") (pintype "passive"))
      (node (ref "J5") (pin "13") (pinfunction "13_13") (pintype "passive"))
      (node (ref "J6") (pin "13") (pinfunction "13_13") (pintype "passive"))
      (node (ref "J7") (pin "1") (pinfunction "1_1") (pintype "passive"))
      (node (ref "J8") (pin "GND") (pinfunction "GND_GND") (pintype "power_in"))
      (node (ref "J8") (pin "SHIELD1") (pinfunction "SHIELD_SHIELD1") (pintype "bidirectional"))
      (node (ref "J8") (pin "SHIELD2") (pinfunction "SHIELD_SHIELD2") (pintype "bidirectional"))
      (node (ref "J8") (pin "SHIELD3") (pinfunction "SHIELD_SHIELD3") (pintype "bidirectional"))
      (node (ref "K1") (pin "5") (pinfunction "VREFL_5") (pintype "bidirectional"))
      (node (ref "K1") (pin "6") (pinfunction "VSS_6") (pintype "bidirectional"))
      (node (ref "K2") (pin "31") (pinfunction "VSS_31") (pintype "bidirectional"))
      (node (ref "K2") (pin "4") (pinfunction "VSS_4") (pintype "bidirectional"))
      (node (ref "K2") (pin "47") (pinfunction "VSS_47") (pintype "bidirectional"))
      (node (ref "LED2") (pin "C") (pinfunction "C_C") (pintype "passive"))
      (node (ref "R10") (pin "1") (pinfunction "1_1") (pintype "passive"))
      (node (ref "R18") (pin "1") (pinfunction "1_1") (pintype "passive"))
      (node (ref "R19") (pin "1") (pinfunction "1_1") (pintype "passive"))
      (node (ref "R20") (pin "1") (pinfunction "1_1") (pintype "passive"))
      (node (ref "R22") (pin "1") (pinfunction "1_1") (pintype "passive"))
      (node (ref "R3") (pin "1") (pinfunction "1_1") (pintype "passive"))
      (node (ref "S1") (pin "3") (pinfunction "3_3") (pintype "passive"))
      (node (ref "S1") (pin "4") (pinfunction "3_4") (pintype "passive"))
      (node (ref "T1") (pin "2") (pinfunction "GND_2") (pintype "bidirectional"))
      (node (ref "T1") (pin "PAD") (pinfunction "PAD_PAD") (pintype "bidirectional"))
      (node (ref "U1") (pin "6") (pinfunction "GND_6") (pintype "bidirectional"))
      (node (ref "U1") (pin "GND1") (pinfunction "SHIELD1_GND1") (pintype "bidirectional"))
      (node (ref "U1") (pin "GND2") (pinfunction "SHIELD2_GND2") (pintype "bidirectional"))
      (node (ref "U2") (pin "1") (pinfunction "GND_2_1") (pintype "power_in"))
      (node (ref "U2") (pin "3") (pinfunction "GND_3") (pintype "power_in"))
      (node (ref "U2") (pin "31") (pinfunction "CTRIL_ADR0_CS_31") (pintype "passive"))
      (node (ref "U2") (pin "32") (pinfunction "CTRL_MODE_32") (pintype "passive"))
      (node (ref "U2") (pin "7") (pinfunction "AGND_7") (pintype "power_in"))
      (node (ref "U3") (pin "3") (pinfunction "GND_3") (pintype "power_in"))
      (node (ref "U4") (pin "2") (pinfunction "VSS_2") (pintype "power_in"))
      (node (ref "U5") (pin "1") (pinfunction "GND_1") (pintype "bidirectional"))
      (node (ref "U5") (pin "12") (pinfunction "GND1_12") (pintype "bidirectional"))
      (node (ref "U5") (pin "25") (pinfunction "GND2_25") (pintype "bidirectional"))
      (node (ref "U5") (pin "27") (pinfunction "GND3_27") (pintype "bidirectional"))
      (node (ref "U5") (pin "28") (pinfunction "GND4_28") (pintype "bidirectional"))
      (node (ref "U5") (pin "29") (pinfunction "GND5_29") (pintype "bidirectional"))
    )
    (net (code "61") (name "Net-(J8-PadD+)") (class "Default")
      (node (ref "J8") (pin "D+") (pinfunction "D+_D+") (pintype "bidirectional"))
      (node (ref "R7") (pin "1") (pinfunction "1_1") (pintype "passive"))
    )
    (net (code "62") (name "Net-(J8-PadD-)") (class "Default")
      (node (ref "J8") (pin "D-") (pinfunction "D-_D-") (pintype "bidirectional"))
      (node (ref "R6") (pin "1") (pinfunction "1_1") (pintype "passive"))
    )
    (net (code "63") (name "Net-(K1-PTA7)") (class "Default")
      (node (ref "K1") (pin "15") (pinfunction "PTA7_15") (pintype "bidirectional"))
      (node (ref "K2") (pin "25") (pinfunction "PTA3_25") (pintype "bidirectional"))
    )
    (net (code "64") (name "Net-(K1-PTB0)") (class "Default")
      (node (ref "K1") (pin "16") (pinfunction "PTB0_16") (pintype "bidirectional"))
      (node (ref "K2") (pin "22") (pinfunction "PTA0_22") (pintype "bidirectional"))
    )
    (net (code "65") (name "Net-(K1-PTB1)") (class "Default")
      (node (ref "K1") (pin "17") (pinfunction "PTB1_17") (pintype "bidirectional"))
      (node (ref "K2") (pin "24") (pinfunction "PTA2_24") (pintype "bidirectional"))
    )
    (net (code "66") (name "Net-(K2-PTA18)") (class "Default")
      (node (ref "C8") (pin "1") (pinfunction "1_1") (pintype "passive"))
      (node (ref "G1") (pin "1") (pinfunction "1_1") (pintype "passive"))
      (node (ref "K2") (pin "32") (pinfunction "PTA18_32") (pintype "bidirectional"))
    )
    (net (code "67") (name "Net-(K2-PTA19)") (class "Default")
      (node (ref "C11") (pin "1") (pinfunction "1_1") (pintype "passive"))
      (node (ref "G1") (pin "2") (pinfunction "2_2") (pintype "passive"))
      (node (ref "K2") (pin "33") (pinfunction "PTA19_33") (pintype "bidirectional"))
    )
    (net (code "68") (name "Net-(K2-USB0_DM)") (class "Default")
      (node (ref "K2") (pin "6") (pinfunction "USB0_DM_6") (pintype "bidirectional"))
      (node (ref "R6") (pin "2") (pinfunction "2_2") (pintype "passive"))
    )
    (net (code "69") (name "Net-(K2-USB0_DP)") (class "Default")
      (node (ref "K2") (pin "5") (pinfunction "USB0_DP_5") (pintype "bidirectional"))
      (node (ref "R7") (pin "2") (pinfunction "2_2") (pintype "passive"))
    )
    (net (code "70") (name "Net-(K2-VBAT)") (class "Default")
      (node (ref "C3") (pin "1") (pinfunction "1_1") (pintype "passive"))
      (node (ref "K2") (pin "21") (pinfunction "VBAT_21") (pintype "bidirectional"))
      (node (ref "R2") (pin "3") (pinfunction "3_3") (pintype "bidirectional"))
    )
    (net (code "71") (name "Net-(K2-VDDA)") (class "Default")
      (node (ref "C5") (pin "1") (pinfunction "1_1") (pintype "passive"))
      (node (ref "K2") (pin "13") (pinfunction "VDDA_13") (pintype "bidirectional"))
      (node (ref "R4") (pin "1") (pinfunction "1_1") (pintype "passive"))
      (node (ref "R5") (pin "1") (pinfunction "1_1") (pintype "passive"))
    )
    (net (code "72") (name "Net-(K2-VREF_OUT)") (class "Default")
      (node (ref "C17") (pin "1") (pinfunction "1_1") (pintype "passive"))
      (node (ref "K2") (pin "17") (pinfunction "VREF_OUT_17") (pintype "bidirectional"))
    )
    (net (code "73") (name "Net-(LED1-PadC)") (class "Default")
      (node (ref "LED1") (pin "C") (pinfunction "C_C") (pintype "passive"))
      (node (ref "R10") (pin "2") (pinfunction "2_2") (pintype "passive"))
    )
    (net (code "74") (name "Net-(LED2-PadA)") (class "Default")
      (node (ref "LED2") (pin "A") (pinfunction "A_A") (pintype "passive"))
      (node (ref "R15") (pin "1") (pinfunction "1_1") (pintype "passive"))
    )
    (net (code "75") (name "Net-(LED3-PadC)") (class "Default")
      (node (ref "LED3") (pin "C") (pinfunction "C_C") (pintype "passive"))
      (node (ref "R14") (pin "1") (pinfunction "1_1") (pintype "passive"))
    )
    (net (code "76") (name "Net-(LED4-PadC)") (class "Default")
      (node (ref "LED4") (pin "C") (pinfunction "C_C") (pintype "passive"))
      (node (ref "R18") (pin "2") (pinfunction "2_2") (pintype "passive"))
    )
    (net (code "77") (name "Net-(LED5-PadC)") (class "Default")
      (node (ref "LED5") (pin "C") (pinfunction "C_C") (pintype "passive"))
      (node (ref "R22") (pin "2") (pinfunction "2_2") (pintype "passive"))
    )
    (net (code "78") (name "Net-(R21-Pad2)") (class "Default")
      (node (ref "R21") (pin "2") (pinfunction "2_2") (pintype "bidirectional"))
      (node (ref "SJ3") (pin "2") (pinfunction "2_2") (pintype "passive"))
    )
    (net (code "79") (name "Net-(U2-I2S_DIN)") (class "Default")
      (node (ref "SJ1") (pin "1") (pinfunction "1_1") (pintype "passive"))
      (node (ref "U2") (pin "26") (pinfunction "I2S_DIN_26") (pintype "input"))
    )
    (net (code "80") (name "Net-(U2-I2S_DOUT)") (class "Default")
      (node (ref "SJ2") (pin "1") (pinfunction "1_1") (pintype "passive"))
      (node (ref "U2") (pin "25") (pinfunction "I2S_DOUT_25") (pintype "output"))
    )
    (net (code "81") (name "Net-(U2-LINEIN_L)") (class "Default")
      (node (ref "C10") (pin "1") (pinfunction "1_1") (pintype "passive"))
      (node (ref "U2") (pin "14") (pinfunction "LINEIN_L_14") (pintype "input"))
    )
    (net (code "82") (name "Net-(U2-LINEIN_R)") (class "Default")
      (node (ref "C9") (pin "1") (pinfunction "1_1") (pintype "passive"))
      (node (ref "U2") (pin "13") (pinfunction "LINEIN_R_13") (pintype "input"))
    )
    (net (code "83") (name "Net-(U2-LINEOUT_L)") (class "Default")
      (node (ref "C7") (pin "1") (pinfunction "1_1") (pintype "passive"))
      (node (ref "U2") (pin "12") (pinfunction "LINEOUT_L_12") (pintype "output"))
    )
    (net (code "84") (name "Net-(U2-LINEOUT_R)") (class "Default")
      (node (ref "C6") (pin "1") (pinfunction "1_1") (pintype "passive"))
      (node (ref "U2") (pin "11") (pinfunction "LINEOUT_R_11") (pintype "output"))
    )
    (net (code "85") (name "Net-(U2-MIC)") (class "Default")
      (node (ref "C18") (pin "1") (pinfunction "1_1") (pintype "passive"))
      (node (ref "U2") (pin "15") (pinfunction "MIC_15") (pintype "input"))
    )
    (net (code "86") (name "Net-(U2-MIC_BIAS)") (class "Default")
      (node (ref "C20") (pin "1") (pinfunction "1_1") (pintype "passive"))
      (node (ref "R9") (pin "2") (pinfunction "2_2") (pintype "passive"))
      (node (ref "U2") (pin "16") (pinfunction "MIC_BIAS_16") (pintype "passive"))
    )
    (net (code "87") (name "Net-(U2-VAG)") (class "Default")
      (node (ref "C14") (pin "1") (pinfunction "1_1") (pintype "passive"))
      (node (ref "U2") (pin "10") (pinfunction "VAG_10") (pintype "passive"))
    )
    (net (code "88") (name "Net-(U2-VDDA)") (class "Default")
      (node (ref "C19") (pin "1") (pinfunction "1_1") (pintype "passive"))
      (node (ref "R8") (pin "1") (pinfunction "1_1") (pintype "passive"))
      (node (ref "U2") (pin "5") (pinfunction "VDDA_5") (pintype "power_in"))
    )
    (net (code "89") (name "Net-(U2-VDDD)") (class "Default")
      (node (ref "U2") (pin "30") (pinfunction "VDDD_30") (pintype "power_in"))
      (node (ref "U3") (pin "2") (pinfunction "OUT_2") (pintype "output"))
    )
    (net (code "90") (name "Net-(U4-PROG)") (class "Default")
      (node (ref "R19") (pin "2") (pinfunction "2_2") (pintype "passive"))
      (node (ref "U4") (pin "5") (pinfunction "PROG_5") (pintype "input"))
    )
    (net (code "91") (name "Net-(U4-STAT)") (class "Default")
      (node (ref "R14") (pin "2") (pinfunction "2_2") (pintype "passive"))
      (node (ref "R15") (pin "2") (pinfunction "2_2") (pintype "passive"))
      (node (ref "U4") (pin "1") (pinfunction "STAT_1") (pintype "output"))
    )
    (net (code "92") (name "Net-(U4-VBAT)") (class "Default")
      (node (ref "C22") (pin "1") (pinfunction "1_1") (pintype "passive"))
      (node (ref "CN1") (pin "2") (pinfunction "2_2") (pintype "passive"))
      (node (ref "R21") (pin "1") (pinfunction "1_1") (pintype "bidirectional"))
      (node (ref "U4") (pin "3") (pinfunction "VBAT_3") (pintype "power_in"))
    )
    (net (code "93") (name "Net-(U5-PIO2)") (class "Default")
      (node (ref "LED5") (pin "A") (pinfunction "A_A") (pintype "passive"))
      (node (ref "U5") (pin "19") (pinfunction "PIO2_19") (pintype "bidirectional"))
    )
    (net (code "94") (name "Net-(U5-PIO4)") (class "Default")
      (node (ref "JP1") (pin "1") (pinfunction "1_1") (pintype "passive"))
      (node (ref "R20") (pin "2") (pinfunction "2_2") (pintype "passive"))
      (node (ref "U5") (pin "22") (pinfunction "PIO4_22") (pintype "bidirectional"))
    )
    (net (code "95") (name "Net-(U5-PIO5)") (class "Default")
      (node (ref "LED4") (pin "A") (pinfunction "A_A") (pintype "passive"))
      (node (ref "U5") (pin "21") (pinfunction "PIO5_21") (pintype "bidirectional"))
    )
    (net (code "96") (name "VIN") (class "Default")
      (node (ref "C4") (pin "1") (pinfunction "1_1") (pintype "passive"))
      (node (ref "J2") (pin "4") (pinfunction "4_4") (pintype "passive"))
      (node (ref "J5") (pin "14") (pinfunction "14_14") (pintype "passive"))
      (node (ref "J6") (pin "14") (pinfunction "14_14") (pintype "passive"))
      (node (ref "R13") (pin "1") (pinfunction "1_1") (pintype "passive"))
      (node (ref "R21") (pin "3") (pinfunction "3_3") (pintype "bidirectional"))
      (node (ref "T1") (pin "1") (pinfunction "IN_1") (pintype "bidirectional"))
      (node (ref "U3") (pin "1") (pinfunction "IN_1") (pintype "input"))
    )
    (net (code "97") (name "V_USB") (class "Default")
      (node (ref "C1") (pin "1") (pinfunction "1_1") (pintype "passive"))
      (node (ref "C21") (pin "1") (pinfunction "1_1") (pintype "passive"))
      (node (ref "J5") (pin "1") (pinfunction "1_1") (pintype "passive"))
      (node (ref "J8") (pin "VBUS") (pinfunction "VBUS_VBUS") (pintype "power_in"))
      (node (ref "LED3") (pin "A") (pinfunction "A_A") (pintype "passive"))
      (node (ref "SJ3") (pin "1") (pinfunction "1_1") (pintype "passive"))
      (node (ref "U4") (pin "4") (pinfunction "VDD_4") (pintype "power_in"))
    )
    (net (code "98") (name "unconnected-(J3-PadRING2)") (class "Default")
      (node (ref "J3") (pin "RING2") (pinfunction "RING2_RING2") (pintype "bidirectional"))
    )
    (net (code "99") (name "unconnected-(K1-PTA0-Pad30)") (class "Default")
      (node (ref "K1") (pin "30") (pinfunction "PTA0_30") (pintype "bidirectional"))
    )
    (net (code "100") (name "unconnected-(K1-PTA1-Pad31)") (class "Default")
      (node (ref "K1") (pin "31") (pinfunction "PTA1_31") (pintype "bidirectional"))
    )
    (net (code "101") (name "unconnected-(K1-PTA2-Pad32)") (class "Default")
      (node (ref "K1") (pin "32") (pinfunction "PTA2_32") (pintype "bidirectional"))
    )
    (net (code "102") (name "unconnected-(K1-PTA3-Pad7)") (class "Default")
      (node (ref "K1") (pin "7") (pinfunction "PTA3_7") (pintype "bidirectional"))
    )
    (net (code "103") (name "unconnected-(K1-PTA5-Pad9)") (class "Default")
      (node (ref "K1") (pin "9") (pinfunction "PTA5_9") (pintype "bidirectional"))
    )
    (net (code "104") (name "unconnected-(K1-PTB3-Pad23)") (class "Default")
      (node (ref "K1") (pin "23") (pinfunction "PTB3_23") (pintype "bidirectional"))
    )
    (net (code "105") (name "unconnected-(K1-PTB4-Pad24)") (class "Default")
      (node (ref "K1") (pin "24") (pinfunction "PTB4_24") (pintype "bidirectional"))
    )
    (net (code "106") (name "unconnected-(K2-EXTAL32-Pad20)") (class "Default")
      (node (ref "K2") (pin "20") (pinfunction "EXTAL32_20") (pintype "bidirectional"))
    )
    (net (code "107") (name "unconnected-(K2-VREGIN-Pad8)") (class "Default")
      (node (ref "K2") (pin "8") (pinfunction "VREGIN_8") (pintype "bidirectional"))
    )
    (net (code "108") (name "unconnected-(K2-XTAL32-Pad19)") (class "Default")
      (node (ref "K2") (pin "19") (pinfunction "XTAL32_19") (pintype "bidirectional"))
    )
    (net (code "109") (name "unconnected-(U1-NC-Pad1)") (class "Default")
      (node (ref "U1") (pin "1") (pinfunction "NC_1") (pintype "bidirectional"))
    )
    (net (code "110") (name "unconnected-(U1-PadCD1)") (class "Default")
      (node (ref "U1") (pin "CD1") (pinfunction "CD1_CD1") (pintype "bidirectional"))
    )
    (net (code "111") (name "unconnected-(U1-RSV-Pad8)") (class "Default")
      (node (ref "U1") (pin "8") (pinfunction "RSV_8") (pintype "bidirectional"))
    )
    (net (code "112") (name "unconnected-(U2-CPFLT-Pad18)") (class "Default")
      (node (ref "U2") (pin "18") (pinfunction "CPFLT_18") (pintype "passive"))
    )
    (net (code "113") (name "unconnected-(U2-NC-Pad28)") (class "Default")
      (node (ref "U2") (pin "28") (pinfunction "NC_28") (pintype "passive"))
    )
    (net (code "114") (name "unconnected-(U2-NC_2-Pad8)") (class "Default")
      (node (ref "U2") (pin "8") (pinfunction "NC_2_8") (pintype "passive"))
    )
    (net (code "115") (name "unconnected-(U2-NC_3-Pad9)") (class "Default")
      (node (ref "U2") (pin "9") (pinfunction "NC_3_9") (pintype "passive"))
    )
    (net (code "116") (name "unconnected-(U2-NC_4-Pad17)") (class "Default")
      (node (ref "U2") (pin "17") (pinfunction "NC_4_17") (pintype "passive"))
    )
    (net (code "117") (name "unconnected-(U2-NC_5-Pad19)") (class "Default")
      (node (ref "U2") (pin "19") (pinfunction "NC_5_19") (pintype "passive"))
    )
    (net (code "118") (name "unconnected-(U2-NC_6-Pad22)") (class "Default")
      (node (ref "U2") (pin "22") (pinfunction "NC_6_22") (pintype "passive"))
    )
    (net (code "119") (name "unconnected-(U5-AIO1-Pad35)") (class "Default")
      (node (ref "U5") (pin "35") (pinfunction "AIO1_35") (pintype "bidirectional"))
    )
    (net (code "120") (name "unconnected-(U5-AIO2-Pad30)") (class "Default")
      (node (ref "U5") (pin "30") (pinfunction "AIO2_30") (pintype "bidirectional"))
    )
    (net (code "121") (name "unconnected-(U5-NC-Pad26)") (class "Default")
      (node (ref "U5") (pin "26") (pinfunction "NC_26") (pintype "bidirectional"))
    )
    (net (code "122") (name "unconnected-(U5-PCMCLK-Pad7)") (class "Default")
      (node (ref "U5") (pin "7") (pinfunction "PCMCLK_7") (pintype "bidirectional"))
    )
    (net (code "123") (name "unconnected-(U5-PCMIN-Pad9)") (class "Default")
      (node (ref "U5") (pin "9") (pinfunction "PCMIN_9") (pintype "bidirectional"))
    )
    (net (code "124") (name "unconnected-(U5-PCMOUT-Pad10)") (class "Default")
      (node (ref "U5") (pin "10") (pinfunction "PCMOUT_10") (pintype "bidirectional"))
    )
    (net (code "125") (name "unconnected-(U5-PCMSYNC-Pad8)") (class "Default")
      (node (ref "U5") (pin "8") (pinfunction "PCMSYNC_8") (pintype "bidirectional"))
    )
    (net (code "126") (name "unconnected-(U5-PIO3-Pad20)") (class "Default")
      (node (ref "U5") (pin "20") (pinfunction "PIO3_20") (pintype "bidirectional"))
    )
    (net (code "127") (name "unconnected-(U5-PIO6-Pad3)") (class "Default")
      (node (ref "U5") (pin "3") (pinfunction "PIO6_3") (pintype "bidirectional"))
    )
    (net (code "128") (name "unconnected-(U5-PIO7-Pad4)") (class "Default")
      (node (ref "U5") (pin "4") (pinfunction "PIO7_4") (pintype "bidirectional"))
    )
    (net (code "129") (name "unconnected-(U5-PIO8-Pad34)") (class "Default")
      (node (ref "U5") (pin "34") (pinfunction "PIO8_34") (pintype "bidirectional"))
    )
    (net (code "130") (name "unconnected-(U5-PIO9-Pad33)") (class "Default")
      (node (ref "U5") (pin "33") (pinfunction "PIO9_33") (pintype "bidirectional"))
    )
    (net (code "131") (name "unconnected-(U5-PIO10-Pad32)") (class "Default")
      (node (ref "U5") (pin "32") (pinfunction "PIO10_32") (pintype "bidirectional"))
    )
    (net (code "132") (name "unconnected-(U5-PIO11-Pad31)") (class "Default")
      (node (ref "U5") (pin "31") (pinfunction "PIO11_31") (pintype "bidirectional"))
    )
    (net (code "133") (name "unconnected-(U5-RESET-Pad5)") (class "Default")
      (node (ref "U5") (pin "5") (pinfunction "RESET_5") (pintype "bidirectional"))
    )
    (net (code "134") (name "unconnected-(U5-SPICLK-Pad6)") (class "Default")
      (node (ref "U5") (pin "6") (pinfunction "SPICLK_6") (pintype "bidirectional"))
    )
    (net (code "135") (name "unconnected-(U5-SPICSB-Pad23)") (class "Default")
      (node (ref "U5") (pin "23") (pinfunction "SPICSB_23") (pintype "bidirectional"))
    )
    (net (code "136") (name "unconnected-(U5-SPIMISO-Pad24)") (class "Default")
      (node (ref "U5") (pin "24") (pinfunction "SPIMISO_24") (pintype "bidirectional"))
    )
    (net (code "137") (name "unconnected-(U5-SPIMOSI-Pad2)") (class "Default")
      (node (ref "U5") (pin "2") (pinfunction "SPIMOSI_2") (pintype "bidirectional"))
    )
    (net (code "138") (name "unconnected-(U5-USBD+-Pad17)") (class "Default")
      (node (ref "U5") (pin "17") (pinfunction "USBD+_17") (pintype "bidirectional"))
    )
    (net (code "139") (name "unconnected-(U5-USBD--Pad18)") (class "Default")
      (node (ref "U5") (pin "18") (pinfunction "USBD-_18") (pintype "bidirectional"))
    )
  )
)
